# Sheet_IRFS7530_bridges.net
KiCad netlist of a schematic drawn in Altium Designer
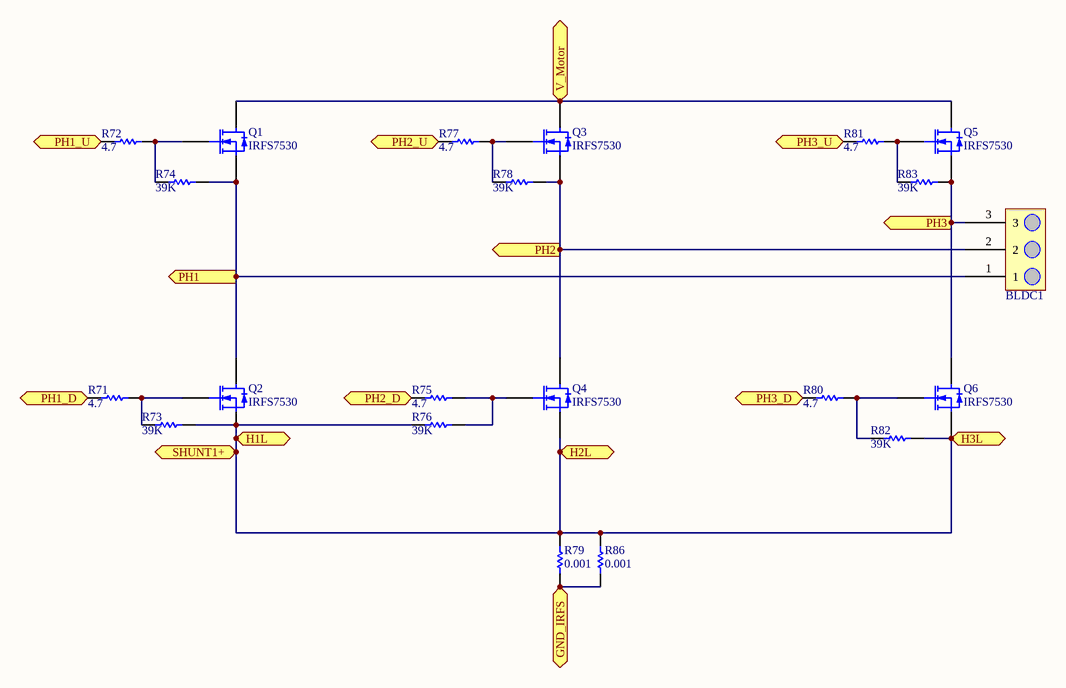
[diagram p0: Sheet_IRFS7530_bridges.SchDoc]

(export (version "E")
  (design (tool "Eeschema 10.0.6"))
  (components
    (comp (ref "BLDC1")
      (value "Terminal3")
      (footprint "ARPG_PCB_LIB:TERM3")
      (description "Connector")
      (libsource (lib "AlmaLib1") (part "Terminal3"))
    )
    (comp (ref "Q1")
      (value "IRFS7530")
      (footprint "ARPG_PCB_LIB:D2PAK-7Pin")
      (libsource (lib "AlmaLib1") (part "IRFS7530"))
    )
    (comp (ref "Q2")
      (value "IRFS7530")
      (footprint "ARPG_PCB_LIB:D2PAK-7Pin")
      (libsource (lib "AlmaLib1") (part "IRFS7530"))
    )
    (comp (ref "Q3")
      (value "IRFS7530")
      (footprint "ARPG_PCB_LIB:D2PAK-7Pin")
      (libsource (lib "AlmaLib1") (part "IRFS7530"))
    )
    (comp (ref "Q4")
      (value "IRFS7530")
      (footprint "ARPG_PCB_LIB:D2PAK-7Pin")
      (libsource (lib "AlmaLib1") (part "IRFS7530"))
    )
    (comp (ref "Q5")
      (value "IRFS7530")
      (footprint "ARPG_PCB_LIB:D2PAK-7Pin")
      (libsource (lib "AlmaLib1") (part "IRFS7530"))
    )
    (comp (ref "Q6")
      (value "IRFS7530")
      (footprint "ARPG_PCB_LIB:D2PAK-7Pin")
      (libsource (lib "AlmaLib1") (part "IRFS7530"))
    )
    (comp (ref "R71")
      (value "4.7")
      (footprint "ARPG_PCB_LIB:1608[0603]")
      (description "Res")
      (libsource (lib "AlmaLib1") (part "Res"))
    )
    (comp (ref "R72")
      (value "4.7")
      (footprint "ARPG_PCB_LIB:1608[0603]")
      (description "Res")
      (libsource (lib "AlmaLib1") (part "Res"))
    )
    (comp (ref "R73")
      (value "39K")
      (footprint "ARPG_PCB_LIB:1608[0603]")
      (description "Res")
      (libsource (lib "AlmaLib1") (part "Res"))
    )
    (comp (ref "R74")
      (value "39K")
      (footprint "ARPG_PCB_LIB:1608[0603]")
      (description "Res")
      (libsource (lib "AlmaLib1") (part "Res"))
    )
    (comp (ref "R75")
      (value "4.7")
      (footprint "ARPG_PCB_LIB:1608[0603]")
      (description "Res")
      (libsource (lib "AlmaLib1") (part "Res"))
    )
    (comp (ref "R76")
      (value "39K")
      (footprint "ARPG_PCB_LIB:1608[0603]")
      (description "Res")
      (libsource (lib "AlmaLib1") (part "Res"))
    )
    (comp (ref "R77")
      (value "4.7")
      (footprint "ARPG_PCB_LIB:1608[0603]")
      (description "Res")
      (libsource (lib "AlmaLib1") (part "Res"))
    )
    (comp (ref "R78")
      (value "39K")
      (footprint "ARPG_PCB_LIB:1608[0603]")
      (description "Res")
      (libsource (lib "AlmaLib1") (part "Res"))
    )
    (comp (ref "R79")
      (value "0.001")
      (footprint "ARPG_PCB_LIB:5931")
      (description "Res")
      (libsource (lib "AlmaLib1") (part "Res"))
    )
    (comp (ref "R80")
      (value "4.7")
      (footprint "ARPG_PCB_LIB:1608[0603]")
      (description "Res")
      (libsource (lib "AlmaLib1") (part "Res"))
    )
    (comp (ref "R81")
      (value "4.7")
      (footprint "ARPG_PCB_LIB:1608[0603]")
      (description "Res")
      (libsource (lib "AlmaLib1") (part "Res"))
    )
    (comp (ref "R82")
      (value "39K")
      (footprint "ARPG_PCB_LIB:1608[0603]")
      (description "Res")
      (libsource (lib "AlmaLib1") (part "Res"))
    )
    (comp (ref "R83")
      (value "39K")
      (footprint "ARPG_PCB_LIB:1608[0603]")
      (description "Res")
      (libsource (lib "AlmaLib1") (part "Res"))
    )
    (comp (ref "R86")
      (value "0.001")
      (footprint "ARPG_PCB_LIB:5931")
      (description "Res")
      (libsource (lib "AlmaLib1") (part "Res"))
    )
  )
  (nets
    (net (code "1") (name "/GND_IRFS") (class "Default")
      (node (ref "R79") (pin "1") (pinfunction "1_1") (pintype "passive"))
      (node (ref "R86") (pin "1") (pinfunction "1_1") (pintype "passive"))
    )
    (net (code "2") (name "/H1L") (class "Default")
      (node (ref "Q2") (pin "3") (pinfunction "S_3") (pintype "passive"))
      (node (ref "Q4") (pin "3") (pinfunction "S_3") (pintype "passive"))
      (node (ref "Q6") (pin "3") (pinfunction "S_3") (pintype "passive"))
      (node (ref "R73") (pin "2") (pinfunction "2_2") (pintype "passive"))
      (node (ref "R76") (pin "1") (pinfunction "1_1") (pintype "passive"))
      (node (ref "R79") (pin "2") (pinfunction "2_2") (pintype "passive"))
      (node (ref "R82") (pin "2") (pinfunction "2_2") (pintype "passive"))
      (node (ref "R86") (pin "2") (pinfunction "2_2") (pintype "passive"))
    )
    (net (code "3") (name "/PH1") (class "Default")
      (node (ref "BLDC1") (pin "1") (pinfunction "1_1") (pintype "passive"))
      (node (ref "Q1") (pin "3") (pinfunction "S_3") (pintype "passive"))
      (node (ref "Q2") (pin "2") (pinfunction "D_2") (pintype "passive"))
      (node (ref "R74") (pin "2") (pinfunction "2_2") (pintype "passive"))
    )
    (net (code "4") (name "/PH1_D") (class "Default")
      (node (ref "R71") (pin "1") (pinfunction "1_1") (pintype "passive"))
    )
    (net (code "5") (name "/PH1_U") (class "Default")
      (node (ref "R72") (pin "1") (pinfunction "1_1") (pintype "passive"))
    )
    (net (code "6") (name "/PH2") (class "Default")
      (node (ref "BLDC1") (pin "2") (pinfunction "2_2") (pintype "passive"))
      (node (ref "Q3") (pin "3") (pinfunction "S_3") (pintype "passive"))
      (node (ref "Q4") (pin "2") (pinfunction "D_2") (pintype "passive"))
      (node (ref "R78") (pin "2") (pinfunction "2_2") (pintype "passive"))
    )
    (net (code "7") (name "/PH2_D") (class "Default")
      (node (ref "R75") (pin "1") (pinfunction "1_1") (pintype "passive"))
    )
    (net (code "8") (name "/PH2_U") (class "Default")
      (node (ref "R77") (pin "1") (pinfunction "1_1") (pintype "passive"))
    )
    (net (code "9") (name "/PH3") (class "Default")
      (node (ref "BLDC1") (pin "3") (pinfunction "3_3") (pintype "passive"))
      (node (ref "Q5") (pin "3") (pinfunction "S_3") (pintype "passive"))
      (node (ref "Q6") (pin "2") (pinfunction "D_2") (pintype "passive"))
      (node (ref "R83") (pin "2") (pinfunction "2_2") (pintype "passive"))
    )
    (net (code "10") (name "/PH3_D") (class "Default")
      (node (ref "R80") (pin "1") (pinfunction "1_1") (pintype "passive"))
    )
    (net (code "11") (name "/PH3_U") (class "Default")
      (node (ref "R81") (pin "1") (pinfunction "1_1") (pintype "passive"))
    )
    (net (code "12") (name "/V_Motor") (class "Default")
      (node (ref "Q1") (pin "2") (pinfunction "D_2") (pintype "passive"))
      (node (ref "Q3") (pin "2") (pinfunction "D_2") (pintype "passive"))
      (node (ref "Q5") (pin "2") (pinfunction "D_2") (pintype "passive"))
    )
    (net (code "13") (name "Net-(Q1-G)") (class "Default")
      (node (ref "Q1") (pin "1") (pinfunction "G_1") (pintype "passive"))
      (node (ref "R72") (pin "2") (pinfunction "2_2") (pintype "passive"))
      (node (ref "R74") (pin "1") (pinfunction "1_1") (pintype "passive"))
    )
    (net (code "14") (name "Net-(Q2-G)") (class "Default")
      (node (ref "Q2") (pin "1") (pinfunction "G_1") (pintype "passive"))
      (node (ref "R71") (pin "2") (pinfunction "2_2") (pintype "passive"))
      (node (ref "R73") (pin "1") (pinfunction "1_1") (pintype "passive"))
    )
    (net (code "15") (name "Net-(Q3-G)") (class "Default")
      (node (ref "Q3") (pin "1") (pinfunction "G_1") (pintype "passive"))
      (node (ref "R77") (pin "2") (pinfunction "2_2") (pintype "passive"))
      (node (ref "R78") (pin "1") (pinfunction "1_1") (pintype "passive"))
    )
    (net (code "16") (name "Net-(Q4-G)") (class "Default")
      (node (ref "Q4") (pin "1") (pinfunction "G_1") (pintype "passive"))
      (node (ref "R75") (pin "2") (pinfunction "2_2") (pintype "passive"))
      (node (ref "R76") (pin "2") (pinfunction "2_2") (pintype "passive"))
    )
    (net (code "17") (name "Net-(Q5-G)") (class "Default")
      (node (ref "Q5") (pin "1") (pinfunction "G_1") (pintype "passive"))
      (node (ref "R81") (pin "2") (pinfunction "2_2") (pintype "passive"))
      (node (ref "R83") (pin "1") (pinfunction "1_1") (pintype "passive"))
    )
    (net (code "18") (name "Net-(Q6-G)") (class "Default")
      (node (ref "Q6") (pin "1") (pinfunction "G_1") (pintype "passive"))
      (node (ref "R80") (pin "2") (pinfunction "2_2") (pintype "passive"))
      (node (ref "R82") (pin "1") (pinfunction "1_1") (pintype "passive"))
    )
  )
)
